# BLE-LORA-Relay-22dbm-v1-1.net
KiCad netlist of a schematic drawn in EAGLE
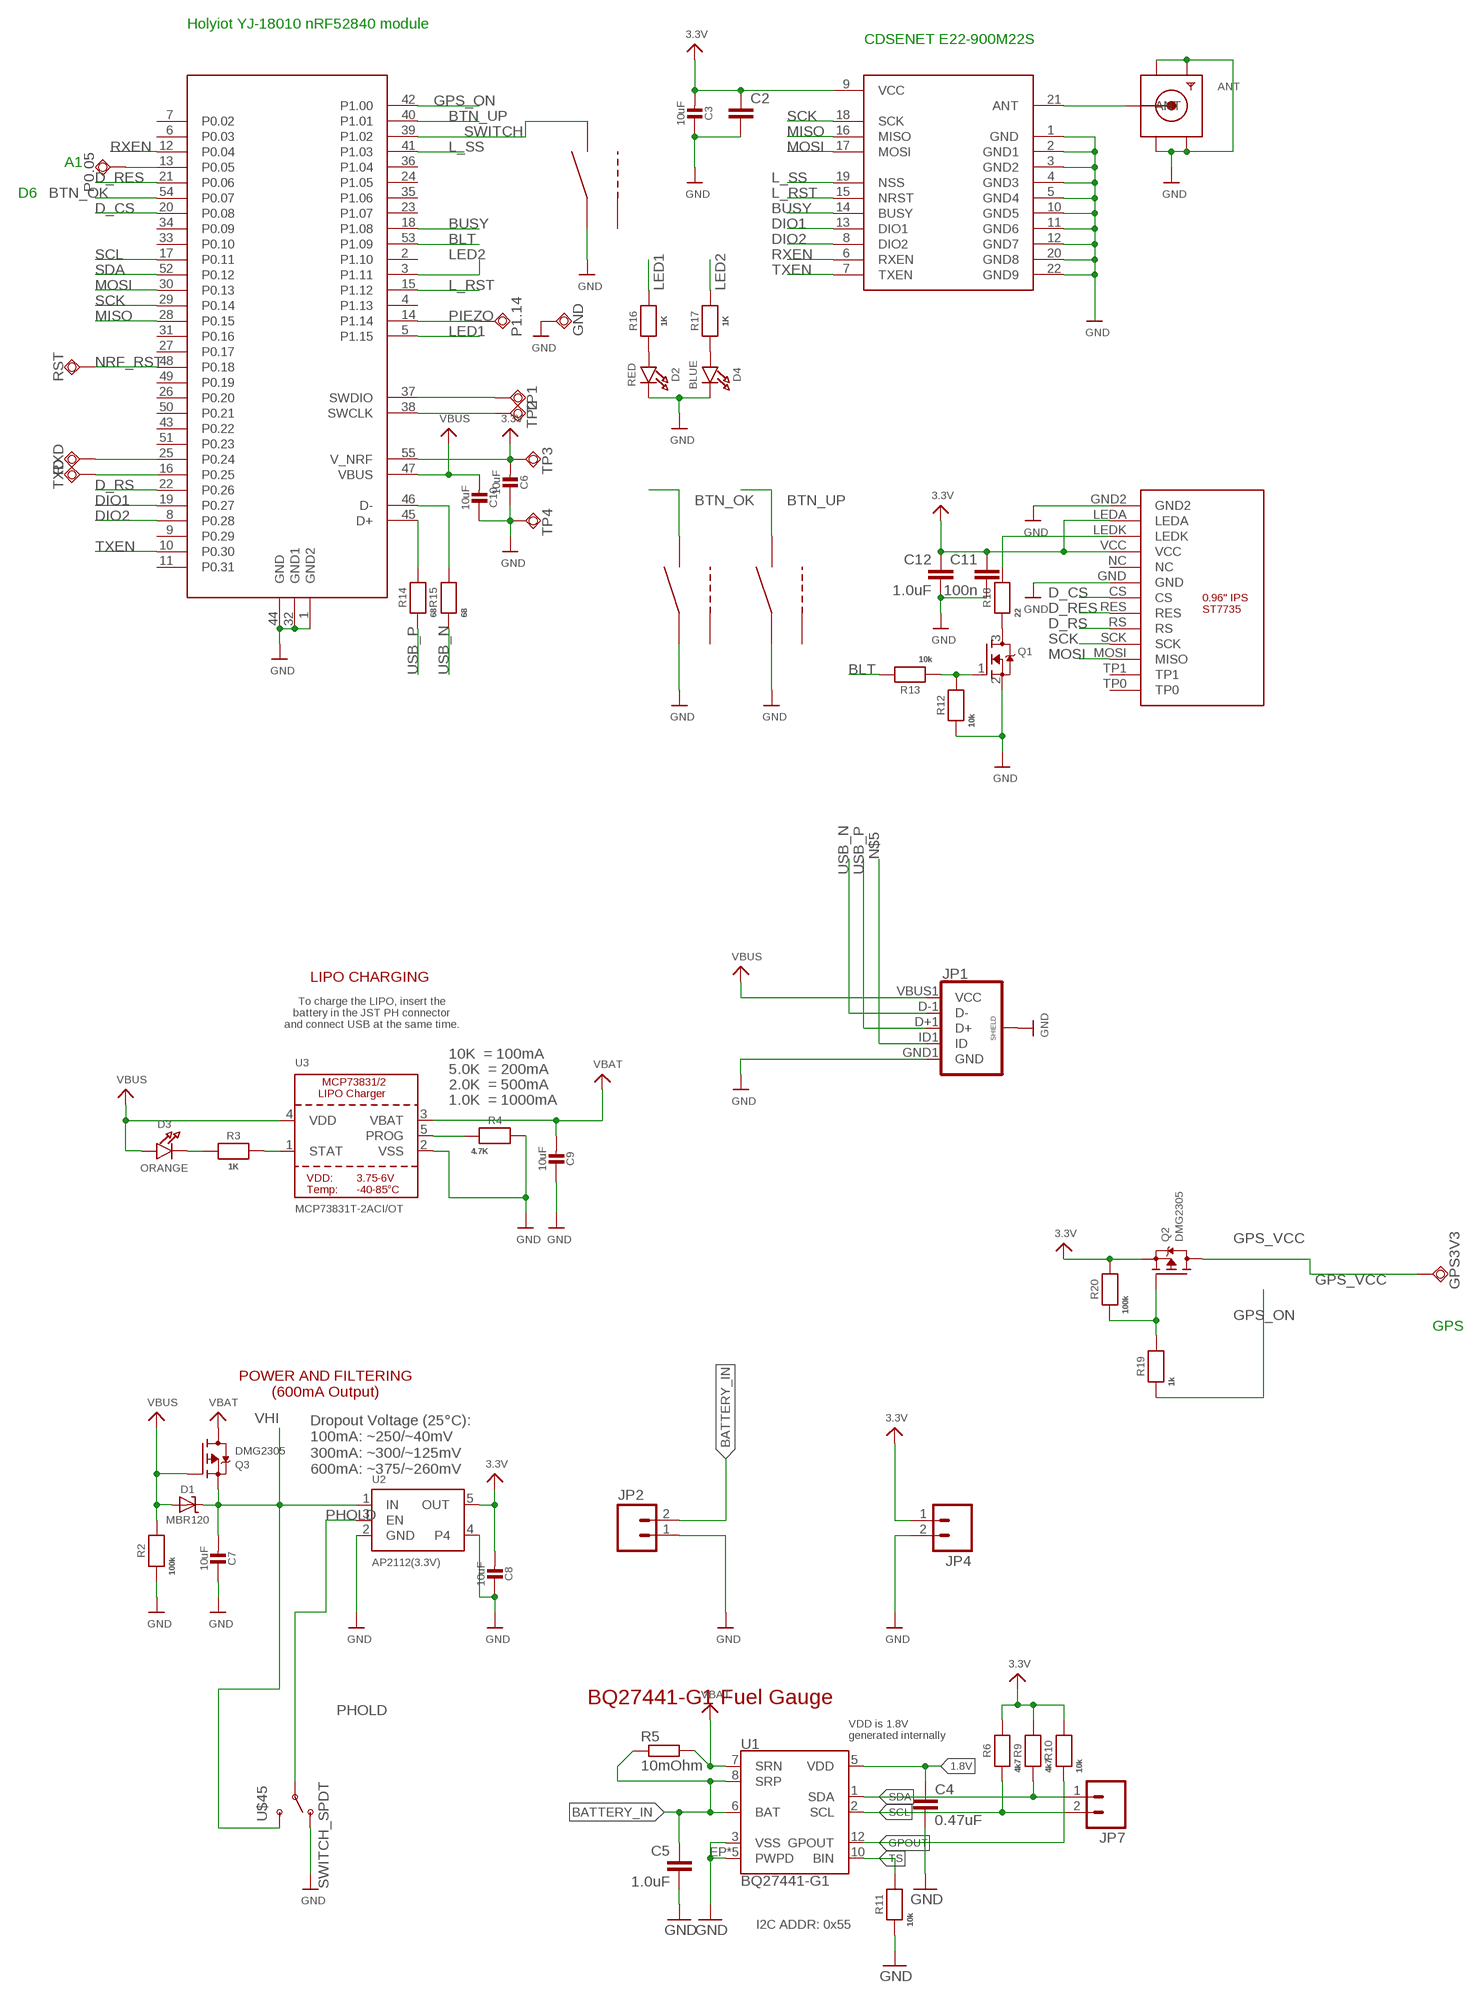
[diagram p0: schematic, sheet 1]

(export (version "E")
  (design (tool "Eeschema 10.0.6"))
  (components
    (comp (ref "ANT")
      (value "SMACONNECTOR_EDGE")
      (footprint "eagle-import:SMA_EDGELAUNCH")
      (libsource (lib "eagle-import") (part "SMACONNECTOR_EDGE"))
    )
    (comp (ref "C2")
      (value "C-EUC1206")
      (footprint "eagle-import:C1206")
      (libsource (lib "eagle-import") (part "C-EUC1206"))
    )
    (comp (ref "C3")
      (value "10uF")
      (footprint "eagle-import:0805-NO")
      (libsource (lib "eagle-import") (part "CAP_CERAMIC0805-NOOUTLINE"))
    )
    (comp (ref "C4")
      (value "0.47uF")
      (footprint "eagle-import:0603-CAP")
      (libsource (lib "eagle-import") (part "CAP0603-CAP"))
    )
    (comp (ref "C5")
      (value "1.0uF")
      (footprint "eagle-import:0603-CAP")
      (libsource (lib "eagle-import") (part "1.0UF-16V-10%(0603)"))
    )
    (comp (ref "C6")
      (value "10uF")
      (footprint "eagle-import:0805-NO")
      (libsource (lib "eagle-import") (part "CAP_CERAMIC0805-NOOUTLINE"))
    )
    (comp (ref "C7")
      (value "10uF")
      (footprint "eagle-import:0805-NO")
      (libsource (lib "eagle-import") (part "CAP_CERAMIC0805-NOOUTLINE"))
    )
    (comp (ref "C8")
      (value "10uF")
      (footprint "eagle-import:0805-NO")
      (libsource (lib "eagle-import") (part "CAP_CERAMIC0805-NOOUTLINE"))
    )
    (comp (ref "C9")
      (value "10uF")
      (footprint "eagle-import:0805-NO")
      (libsource (lib "eagle-import") (part "CAP_CERAMIC0805-NOOUTLINE"))
    )
    (comp (ref "C10")
      (value "10uF")
      (footprint "eagle-import:0805-NO")
      (libsource (lib "eagle-import") (part "CAP_CERAMIC0805-NOOUTLINE"))
    )
    (comp (ref "C11")
      (value "100n")
      (footprint "eagle-import:0603-CAP")
      (libsource (lib "eagle-import") (part "1.0UF-16V-10%(0603)"))
    )
    (comp (ref "C12")
      (value "1.0uF")
      (footprint "eagle-import:0603-CAP")
      (libsource (lib "eagle-import") (part "1.0UF-16V-10%(0603)"))
    )
    (comp (ref "D1")
      (value "MBR120")
      (footprint "eagle-import:SOD-123")
      (libsource (lib "eagle-import") (part "DIODE-SCHOTTKYSOD-123"))
    )
    (comp (ref "D2")
      (value "RED")
      (footprint "eagle-import:CHIPLED_0805_NOOUTLINE")
      (libsource (lib "eagle-import") (part "LED0805_NOOUTLINE"))
    )
    (comp (ref "D3")
      (value "ORANGE")
      (footprint "eagle-import:CHIPLED_0805_NOOUTLINE")
      (libsource (lib "eagle-import") (part "LED0805_NOOUTLINE"))
    )
    (comp (ref "D4")
      (value "BLUE")
      (footprint "eagle-import:CHIPLED_0805_NOOUTLINE")
      (libsource (lib "eagle-import") (part "LED0805_NOOUTLINE"))
    )
    (comp (ref "DWN")
      (value "LS12T2")
      (footprint "eagle-import:LS12T2")
      (libsource (lib "eagle-import") (part "LS12T2"))
    )
    (comp (ref "DWN1")
      (value "LS12T2")
      (footprint "eagle-import:LS12T2")
      (libsource (lib "eagle-import") (part "LS12T2"))
    )
    (comp (ref "DWN2")
      (value "LS12T2")
      (footprint "eagle-import:LS12T2")
      (libsource (lib "eagle-import") (part "LS12T2"))
    )
    (comp (ref "GND")
      (value "TPSQTP13R")
      (footprint "eagle-import:TP13R")
      (libsource (lib "eagle-import") (part "TPSQTP13R"))
    )
    (comp (ref "GPS3V3")
      (value "TPSQTP13R")
      (footprint "eagle-import:TP13R")
      (libsource (lib "eagle-import") (part "TPSQTP13R"))
    )
    (comp (ref "JP1")
      (value "USB_MICROB_PLUGCONN-11752")
      (footprint "eagle-import:USB-B-MICRO-SMD_V03")
      (libsource (lib "eagle-import") (part "USB_MICROB_PLUGCONN-11752"))
    )
    (comp (ref "JP2")
      (value "M02PTH")
      (footprint "eagle-import:1X02")
      (libsource (lib "eagle-import") (part "M02PTH"))
    )
    (comp (ref "JP4")
      (value "M02PTH")
      (footprint "eagle-import:1X02")
      (libsource (lib "eagle-import") (part "M02PTH"))
    )
    (comp (ref "JP7")
      (value "M02PTH")
      (footprint "eagle-import:1X02")
      (libsource (lib "eagle-import") (part "M02PTH"))
    )
    (comp (ref "P0.05")
      (value "TPSQTP13R")
      (footprint "eagle-import:TP13R")
      (libsource (lib "eagle-import") (part "TPSQTP13R"))
    )
    (comp (ref "P1.14")
      (value "TPSQTP13R")
      (footprint "eagle-import:TP13R")
      (libsource (lib "eagle-import") (part "TPSQTP13R"))
    )
    (comp (ref "Q1")
      (value "MOSFET-NREFLOW")
      (footprint "eagle-import:SOT23")
      (libsource (lib "eagle-import") (part "MOSFET-NREFLOW"))
    )
    (comp (ref "Q2")
      (value "DMG2305")
      (footprint "eagle-import:SOT23-R")
      (libsource (lib "eagle-import") (part "MOSFET-P"))
    )
    (comp (ref "Q3")
      (value "DMG2305")
      (footprint "eagle-import:SOT23-R")
      (libsource (lib "eagle-import") (part "MOSFET-P"))
    )
    (comp (ref "R2")
      (value "100k")
      (footprint "eagle-import:0603-NO")
      (libsource (lib "eagle-import") (part "RESISTOR_0603_NOOUT"))
    )
    (comp (ref "R3")
      (value "1K")
      (footprint "eagle-import:0603-NO")
      (libsource (lib "eagle-import") (part "RESISTOR_0603_NOOUT"))
    )
    (comp (ref "R4")
      (value "4.7K")
      (footprint "eagle-import:0603-NO")
      (libsource (lib "eagle-import") (part "RESISTOR_0603_NOOUT"))
    )
    (comp (ref "R5")
      (value "10mOhm")
      (footprint "eagle-import:R0805")
      (libsource (lib "eagle-import") (part "R-EU_R0805"))
    )
    (comp (ref "R6")
      (value "4k7")
      (footprint "eagle-import:0603-NO")
      (libsource (lib "eagle-import") (part "RESISTOR_0603_NOOUT"))
    )
    (comp (ref "R9")
      (value "4k7")
      (footprint "eagle-import:0603-NO")
      (libsource (lib "eagle-import") (part "RESISTOR_0603_NOOUT"))
    )
    (comp (ref "R10")
      (value "10k")
      (footprint "eagle-import:0603-NO")
      (libsource (lib "eagle-import") (part "RESISTOR_0603_NOOUT"))
    )
    (comp (ref "R11")
      (value "10k")
      (footprint "eagle-import:0603-NO")
      (libsource (lib "eagle-import") (part "RESISTOR_0603_NOOUT"))
    )
    (comp (ref "R12")
      (value "10k")
      (footprint "eagle-import:0603-NO")
      (libsource (lib "eagle-import") (part "RESISTOR_0603_NOOUT"))
    )
    (comp (ref "R13")
      (value "10k")
      (footprint "eagle-import:0603-NO")
      (libsource (lib "eagle-import") (part "RESISTOR_0603_NOOUT"))
    )
    (comp (ref "R14")
      (value "68")
      (footprint "eagle-import:0603-NO")
      (libsource (lib "eagle-import") (part "RESISTOR_0603_NOOUT"))
    )
    (comp (ref "R15")
      (value "68")
      (footprint "eagle-import:0603-NO")
      (libsource (lib "eagle-import") (part "RESISTOR_0603_NOOUT"))
    )
    (comp (ref "R16")
      (value "1K")
      (footprint "eagle-import:0603-NO")
      (libsource (lib "eagle-import") (part "RESISTOR_0603_NOOUT"))
    )
    (comp (ref "R17")
      (value "1K")
      (footprint "eagle-import:0603-NO")
      (libsource (lib "eagle-import") (part "RESISTOR_0603_NOOUT"))
    )
    (comp (ref "R18")
      (value "22")
      (footprint "eagle-import:0603-NO")
      (libsource (lib "eagle-import") (part "RESISTOR_0603_NOOUT"))
    )
    (comp (ref "R19")
      (value "1k")
      (footprint "eagle-import:0603-NO")
      (libsource (lib "eagle-import") (part "RESISTOR_0603_NOOUT"))
    )
    (comp (ref "R20")
      (value "100k")
      (footprint "eagle-import:0603-NO")
      (libsource (lib "eagle-import") (part "RESISTOR_0603_NOOUT"))
    )
    (comp (ref "RST")
      (value "TPSQTP13R")
      (footprint "eagle-import:TP13R")
      (libsource (lib "eagle-import") (part "TPSQTP13R"))
    )
    (comp (ref "RXD")
      (value "TPSQTP13R")
      (footprint "eagle-import:TP13R")
      (libsource (lib "eagle-import") (part "TPSQTP13R"))
    )
    (comp (ref "TP1")
      (value "TPSQTP13R")
      (footprint "eagle-import:TP13R")
      (libsource (lib "eagle-import") (part "TPSQTP13R"))
    )
    (comp (ref "TP2")
      (value "TPSQTP13R")
      (footprint "eagle-import:TP13R")
      (libsource (lib "eagle-import") (part "TPSQTP13R"))
    )
    (comp (ref "TP3")
      (value "TPSQTP13R")
      (footprint "eagle-import:TP13R")
      (libsource (lib "eagle-import") (part "TPSQTP13R"))
    )
    (comp (ref "TP4")
      (value "TPSQTP13R")
      (footprint "eagle-import:TP13R")
      (libsource (lib "eagle-import") (part "TPSQTP13R"))
    )
    (comp (ref "TXD")
      (value "TPSQTP13R")
      (footprint "eagle-import:TP13R")
      (libsource (lib "eagle-import") (part "TPSQTP13R"))
    )
    (comp (ref "U$14")
      (value "NRF52840")
      (footprint "eagle-import:NRF52840MOD")
      (libsource (lib "eagle-import") (part "NRF52840"))
    )
    (comp (ref "U$15")
      (value "SX1292-EBYTE")
      (footprint "eagle-import:SX1262_EBYTE")
      (libsource (lib "eagle-import") (part "SX1292-EBYTE"))
    )
    (comp (ref "U$16")
      (value "0.96_IPS")
      (footprint "eagle-import:0.96_IPS")
      (libsource (lib "eagle-import") (part "0.96_IPS"))
    )
    (comp (ref "U$45")
      (value "SWITCH_SPDT")
      (footprint "eagle-import:KPS-1290")
      (libsource (lib "eagle-import") (part "SWITCH_SPDT"))
    )
    (comp (ref "U1")
      (value "BQ27441-G1")
      (footprint "eagle-import:PDSO-N12")
      (libsource (lib "eagle-import") (part "BQ27441-G1"))
    )
    (comp (ref "U2")
      (value "AP2112(3.3V)")
      (footprint "eagle-import:SOT23-5")
      (libsource (lib "eagle-import") (part "VREG_SOT23-5"))
    )
    (comp (ref "U3")
      (value "MCP73831T-2ACI/OT")
      (footprint "eagle-import:SOT23-5")
      (libsource (lib "eagle-import") (part "MCP73831/2"))
    )
  )
  (nets
    (net (code "1") (name "/BLT") (class "Default")
      (node (ref "R13") (pin "2") (pinfunction "2_2") (pintype "passive"))
      (node (ref "U$14") (pin "53") (pinfunction "P1.09_53") (pintype "bidirectional"))
    )
    (net (code "2") (name "/BTN_OK") (class "Default")
      (node (ref "DWN2") (pin "1") (pinfunction "1_1") (pintype "bidirectional"))
      (node (ref "U$14") (pin "54") (pinfunction "P0.07_54") (pintype "bidirectional"))
    )
    (net (code "3") (name "/BTN_UP") (class "Default")
      (node (ref "DWN") (pin "1") (pinfunction "1_1") (pintype "bidirectional"))
      (node (ref "U$14") (pin "40") (pinfunction "P1.01_40") (pintype "bidirectional"))
    )
    (net (code "4") (name "/BUSY") (class "Default")
      (node (ref "U$14") (pin "18") (pinfunction "P1.08_18") (pintype "bidirectional"))
      (node (ref "U$15") (pin "14") (pinfunction "BUSY_14") (pintype "bidirectional"))
    )
    (net (code "5") (name "/DIO1") (class "Default")
      (node (ref "U$14") (pin "19") (pinfunction "P0.27_19") (pintype "bidirectional"))
      (node (ref "U$15") (pin "13") (pinfunction "DIO1_13") (pintype "bidirectional"))
    )
    (net (code "6") (name "/DIO2") (class "Default")
      (node (ref "U$14") (pin "8") (pinfunction "P0.28_8") (pintype "bidirectional"))
      (node (ref "U$15") (pin "8") (pinfunction "DIO2_8") (pintype "bidirectional"))
    )
    (net (code "7") (name "/D_CS") (class "Default")
      (node (ref "U$14") (pin "20") (pinfunction "P0.08_20") (pintype "bidirectional"))
      (node (ref "U$16") (pin "CS") (pinfunction "CS_CS") (pintype "bidirectional"))
    )
    (net (code "8") (name "/D_RES") (class "Default")
      (node (ref "U$14") (pin "21") (pinfunction "P0.06_21") (pintype "bidirectional"))
      (node (ref "U$16") (pin "RES") (pinfunction "RES_RES") (pintype "bidirectional"))
    )
    (net (code "9") (name "/D_RS") (class "Default")
      (node (ref "U$14") (pin "22") (pinfunction "P0.26_22") (pintype "bidirectional"))
      (node (ref "U$16") (pin "RS") (pinfunction "RS_RS") (pintype "bidirectional"))
    )
    (net (code "10") (name "/GPS_ON") (class "Default")
      (node (ref "R19") (pin "1") (pinfunction "1_1") (pintype "passive"))
      (node (ref "U$14") (pin "42") (pinfunction "P1.00_42") (pintype "bidirectional"))
    )
    (net (code "11") (name "/GPS_VCC") (class "Default")
      (node (ref "GPS3V3") (pin "TP") (pinfunction "TP_TP") (pintype "input"))
      (node (ref "Q2") (pin "3") (pinfunction "D_3") (pintype "passive"))
    )
    (net (code "12") (name "/LED1") (class "Default")
      (node (ref "R16") (pin "2") (pinfunction "2_2") (pintype "passive"))
      (node (ref "U$14") (pin "5") (pinfunction "P1.15_5") (pintype "bidirectional"))
    )
    (net (code "13") (name "/LED2") (class "Default")
      (node (ref "R17") (pin "2") (pinfunction "2_2") (pintype "passive"))
      (node (ref "U$14") (pin "3") (pinfunction "P1.11_3") (pintype "bidirectional"))
    )
    (net (code "14") (name "/L_RST") (class "Default")
      (node (ref "U$14") (pin "15") (pinfunction "P1.12_15") (pintype "bidirectional"))
      (node (ref "U$15") (pin "15") (pinfunction "NRST_15") (pintype "bidirectional"))
    )
    (net (code "15") (name "/L_SS") (class "Default")
      (node (ref "U$14") (pin "41") (pinfunction "P1.03_41") (pintype "bidirectional"))
      (node (ref "U$15") (pin "19") (pinfunction "NSS_19") (pintype "bidirectional"))
    )
    (net (code "16") (name "/MISO") (class "Default")
      (node (ref "U$14") (pin "28") (pinfunction "P0.15_28") (pintype "bidirectional"))
      (node (ref "U$15") (pin "16") (pinfunction "MISO_16") (pintype "bidirectional"))
    )
    (net (code "17") (name "/MOSI") (class "Default")
      (node (ref "U$14") (pin "30") (pinfunction "P0.13_30") (pintype "bidirectional"))
      (node (ref "U$15") (pin "17") (pinfunction "MOSI_17") (pintype "bidirectional"))
      (node (ref "U$16") (pin "MOSI") (pinfunction "MISO_MOSI") (pintype "bidirectional"))
    )
    (net (code "18") (name "/N$5") (class "Default")
      (node (ref "JP1") (pin "ID1") (pinfunction "ID_ID1") (pintype "bidirectional"))
    )
    (net (code "19") (name "/NRF_RST") (class "Default")
      (node (ref "RST") (pin "TP") (pinfunction "TP_TP") (pintype "input"))
      (node (ref "U$14") (pin "48") (pinfunction "P0.18_48") (pintype "bidirectional"))
    )
    (net (code "20") (name "/PHOLD") (class "Default")
      (node (ref "U$45") (pin "P") (pinfunction "P_P") (pintype "passive"))
      (node (ref "U2") (pin "3") (pinfunction "EN_3") (pintype "input"))
    )
    (net (code "21") (name "/PIEZO") (class "Default")
      (node (ref "P1.14") (pin "TP") (pinfunction "TP_TP") (pintype "input"))
      (node (ref "U$14") (pin "14") (pinfunction "P1.14_14") (pintype "bidirectional"))
    )
    (net (code "22") (name "/RXEN") (class "Default")
      (node (ref "U$14") (pin "12") (pinfunction "P0.04_12") (pintype "bidirectional"))
      (node (ref "U$15") (pin "6") (pinfunction "RXEN_6") (pintype "bidirectional"))
    )
    (net (code "23") (name "/SCK") (class "Default")
      (node (ref "U$14") (pin "29") (pinfunction "P0.14_29") (pintype "bidirectional"))
      (node (ref "U$15") (pin "18") (pinfunction "SCK_18") (pintype "bidirectional"))
      (node (ref "U$16") (pin "SCK") (pinfunction "SCK_SCK") (pintype "bidirectional"))
    )
    (net (code "24") (name "/SWITCH") (class "Default")
      (node (ref "DWN1") (pin "1") (pinfunction "1_1") (pintype "bidirectional"))
      (node (ref "U$14") (pin "39") (pinfunction "P1.02_39") (pintype "bidirectional"))
    )
    (net (code "25") (name "/TXEN") (class "Default")
      (node (ref "U$14") (pin "10") (pinfunction "P0.30_10") (pintype "bidirectional"))
      (node (ref "U$15") (pin "7") (pinfunction "TXEN_7") (pintype "bidirectional"))
    )
    (net (code "26") (name "/USB_N") (class "Default")
      (node (ref "JP1") (pin "D-1") (pinfunction "D-_D-1") (pintype "bidirectional"))
      (node (ref "R15") (pin "1") (pinfunction "1_1") (pintype "passive"))
    )
    (net (code "27") (name "/USB_P") (class "Default")
      (node (ref "JP1") (pin "D+1") (pinfunction "D+_D+1") (pintype "bidirectional"))
      (node (ref "R14") (pin "1") (pinfunction "1_1") (pintype "passive"))
    )
    (net (code "28") (name "/VHI") (class "Default")
      (node (ref "C7") (pin "2") (pinfunction "2_2") (pintype "passive"))
      (node (ref "D1") (pin "C") (pinfunction "C_C") (pintype "passive"))
      (node (ref "Q3") (pin "2") (pinfunction "S_2") (pintype "passive"))
      (node (ref "U$45") (pin "S") (pinfunction "S_S") (pintype "passive"))
      (node (ref "U2") (pin "1") (pinfunction "IN_1") (pintype "power_in"))
    )
    (net (code "29") (name "1.8V") (class "Default")
      (node (ref "C4") (pin "1") (pinfunction "1_1") (pintype "passive"))
      (node (ref "U1") (pin "5") (pinfunction "VDD_5") (pintype "bidirectional"))
    )
    (net (code "30") (name "3.3V") (class "Default")
      (node (ref "C11") (pin "1") (pinfunction "1_1") (pintype "passive"))
      (node (ref "C12") (pin "1") (pinfunction "1_1") (pintype "passive"))
      (node (ref "C2") (pin "1") (pinfunction "1_1") (pintype "passive"))
      (node (ref "C3") (pin "2") (pinfunction "2_2") (pintype "passive"))
      (node (ref "C6") (pin "2") (pinfunction "2_2") (pintype "passive"))
      (node (ref "C8") (pin "2") (pinfunction "2_2") (pintype "passive"))
      (node (ref "JP4") (pin "1") (pinfunction "1_1") (pintype "passive"))
      (node (ref "Q2") (pin "2") (pinfunction "S_2") (pintype "passive"))
      (node (ref "R10") (pin "2") (pinfunction "2_2") (pintype "passive"))
      (node (ref "R20") (pin "2") (pinfunction "2_2") (pintype "passive"))
      (node (ref "R6") (pin "2") (pinfunction "2_2") (pintype "passive"))
      (node (ref "R9") (pin "2") (pinfunction "2_2") (pintype "passive"))
      (node (ref "TP3") (pin "TP") (pinfunction "TP_TP") (pintype "input"))
      (node (ref "U$14") (pin "55") (pinfunction "V_NRF_55") (pintype "bidirectional"))
      (node (ref "U$15") (pin "9") (pinfunction "VCC_9") (pintype "bidirectional"))
      (node (ref "U$16") (pin "LEDA") (pinfunction "LEDA_LEDA") (pintype "bidirectional"))
      (node (ref "U$16") (pin "VCC") (pinfunction "VCC_VCC") (pintype "bidirectional"))
      (node (ref "U2") (pin "5") (pinfunction "OUT_5") (pintype "power_in"))
    )
    (net (code "31") (name "BATTERY_IN") (class "Default")
      (node (ref "C5") (pin "1") (pinfunction "1_1") (pintype "passive"))
      (node (ref "JP2") (pin "2") (pinfunction "2_2") (pintype "passive"))
      (node (ref "R5") (pin "1") (pinfunction "1_1") (pintype "passive"))
      (node (ref "U1") (pin "6") (pinfunction "BAT_6") (pintype "bidirectional"))
      (node (ref "U1") (pin "8") (pinfunction "SRP_8") (pintype "bidirectional"))
    )
    (net (code "32") (name "GND") (class "Default")
      (node (ref "ANT") (pin "GND@1") (pinfunction "GND4_GND@1") (pintype "power_in"))
      (node (ref "ANT") (pin "GND@2") (pinfunction "GND3_GND@2") (pintype "power_in"))
      (node (ref "ANT") (pin "GND@3") (pinfunction "GND2_GND@3") (pintype "power_in"))
      (node (ref "ANT") (pin "GND@4") (pinfunction "GND1_GND@4") (pintype "power_in"))
      (node (ref "C10") (pin "1") (pinfunction "1_1") (pintype "passive"))
      (node (ref "C11") (pin "2") (pinfunction "2_2") (pintype "passive"))
      (node (ref "C12") (pin "2") (pinfunction "2_2") (pintype "passive"))
      (node (ref "C2") (pin "2") (pinfunction "2_2") (pintype "passive"))
      (node (ref "C3") (pin "1") (pinfunction "1_1") (pintype "passive"))
      (node (ref "C4") (pin "2") (pinfunction "2_2") (pintype "passive"))
      (node (ref "C5") (pin "2") (pinfunction "2_2") (pintype "passive"))
      (node (ref "C6") (pin "1") (pinfunction "1_1") (pintype "passive"))
      (node (ref "C7") (pin "1") (pinfunction "1_1") (pintype "passive"))
      (node (ref "C8") (pin "1") (pinfunction "1_1") (pintype "passive"))
      (node (ref "C9") (pin "1") (pinfunction "1_1") (pintype "passive"))
      (node (ref "D2") (pin "C") (pinfunction "C_C") (pintype "passive"))
      (node (ref "D4") (pin "C") (pinfunction "C_C") (pintype "passive"))
      (node (ref "DWN") (pin "2") (pinfunction "2_2") (pintype "bidirectional"))
      (node (ref "DWN1") (pin "2") (pinfunction "2_2") (pintype "bidirectional"))
      (node (ref "DWN2") (pin "2") (pinfunction "2_2") (pintype "bidirectional"))
      (node (ref "GND") (pin "TP") (pinfunction "TP_TP") (pintype "input"))
      (node (ref "JP1") (pin "GND1") (pinfunction "GND_GND1") (pintype "bidirectional"))
      (node (ref "JP1") (pin "SHIELD1") (pinfunction "SHIELD_SHIELD1") (pintype "bidirectional"))
      (node (ref "JP1") (pin "SHIELD2") (pinfunction "SHIELD_SHIELD2") (pintype "bidirectional"))
      (node (ref "JP1") (pin "SHIELD3") (pinfunction "SHIELD_SHIELD3") (pintype "bidirectional"))
      (node (ref "JP2") (pin "1") (pinfunction "1_1") (pintype "passive"))
      (node (ref "JP4") (pin "2") (pinfunction "2_2") (pintype "passive"))
      (node (ref "Q1") (pin "2") (pinfunction "S_2") (pintype "bidirectional"))
      (node (ref "R11") (pin "1") (pinfunction "1_1") (pintype "passive"))
      (node (ref "R12") (pin "1") (pinfunction "1_1") (pintype "passive"))
      (node (ref "R2") (pin "1") (pinfunction "1_1") (pintype "passive"))
      (node (ref "R4") (pin "2") (pinfunction "2_2") (pintype "passive"))
      (node (ref "TP4") (pin "TP") (pinfunction "TP_TP") (pintype "input"))
      (node (ref "U$14") (pin "1") (pinfunction "GND2_1") (pintype "bidirectional"))
      (node (ref "U$14") (pin "32") (pinfunction "GND1_32") (pintype "bidirectional"))
      (node (ref "U$14") (pin "44") (pinfunction "GND_44") (pintype "bidirectional"))
      (node (ref "U$15") (pin "1") (pinfunction "GND_1") (pintype "bidirectional"))
      (node (ref "U$15") (pin "10") (pinfunction "GND5_10") (pintype "bidirectional"))
      (node (ref "U$15") (pin "11") (pinfunction "GND6_11") (pintype "bidirectional"))
      (node (ref "U$15") (pin "12") (pinfunction "GND7_12") (pintype "bidirectional"))
      (node (ref "U$15") (pin "2") (pinfunction "GND1_2") (pintype "bidirectional"))
      (node (ref "U$15") (pin "20") (pinfunction "GND8_20") (pintype "bidirectional"))
      (node (ref "U$15") (pin "22") (pinfunction "GND9_22") (pintype "bidirectional"))
      (node (ref "U$15") (pin "3") (pinfunction "GND2_3") (pintype "bidirectional"))
      (node (ref "U$15") (pin "4") (pinfunction "GND3_4") (pintype "bidirectional"))
      (node (ref "U$15") (pin "5") (pinfunction "GND4_5") (pintype "bidirectional"))
      (node (ref "U$16") (pin "GND") (pinfunction "GND_GND") (pintype "bidirectional"))
      (node (ref "U$16") (pin "GND2") (pinfunction "GND2_GND2") (pintype "bidirectional"))
      (node (ref "U$45") (pin "O") (pinfunction "O_O") (pintype "passive"))
      (node (ref "U1") (pin "3") (pinfunction "VSS_3") (pintype "bidirectional"))
      (node (ref "U1") (pin "EP") (pinfunction "PWPD_EP") (pintype "bidirectional"))
      (node (ref "U1") (pin "EP1") (pinfunction "PWPD_EP1") (pintype "bidirectional"))
      (node (ref "U1") (pin "EP2") (pinfunction "PWPD_EP2") (pintype "bidirectional"))
      (node (ref "U1") (pin "EP3") (pinfunction "PWPD_EP3") (pintype "bidirectional"))
      (node (ref "U1") (pin "EP4") (pinfunction "PWPD_EP4") (pintype "bidirectional"))
      (node (ref "U2") (pin "2") (pinfunction "GND_2") (pintype "power_in"))
      (node (ref "U2") (pin "4") (pinfunction "P4_4") (pintype "bidirectional"))
      (node (ref "U3") (pin "2") (pinfunction "VSS_2") (pintype "power_in"))
    )
    (net (code "33") (name "GPOUT") (class "Default")
      (node (ref "R10") (pin "1") (pinfunction "1_1") (pintype "passive"))
      (node (ref "U1") (pin "12") (pinfunction "GPOUT_12") (pintype "bidirectional"))
    )
    (net (code "34") (name "Net-(ANT-ANT)") (class "Default")
      (node (ref "ANT") (pin "P") (pinfunction "ANT_P") (pintype "bidirectional"))
      (node (ref "U$15") (pin "21") (pinfunction "ANT_21") (pintype "bidirectional"))
    )
    (net (code "35") (name "Net-(D2-PadA)") (class "Default")
      (node (ref "D2") (pin "A") (pinfunction "A_A") (pintype "passive"))
      (node (ref "R16") (pin "1") (pinfunction "1_1") (pintype "passive"))
    )
    (net (code "36") (name "Net-(D3-PadC)") (class "Default")
      (node (ref "D3") (pin "C") (pinfunction "C_C") (pintype "passive"))
      (node (ref "R3") (pin "1") (pinfunction "1_1") (pintype "passive"))
    )
    (net (code "37") (name "Net-(D4-PadA)") (class "Default")
      (node (ref "D4") (pin "A") (pinfunction "A_A") (pintype "passive"))
      (node (ref "R17") (pin "1") (pinfunction "1_1") (pintype "passive"))
    )
    (net (code "38") (name "Net-(Q1-D)") (class "Default")
      (node (ref "Q1") (pin "3") (pinfunction "D_3") (pintype "bidirectional"))
      (node (ref "R18") (pin "1") (pinfunction "1_1") (pintype "passive"))
    )
    (net (code "39") (name "Net-(Q1-G)") (class "Default")
      (node (ref "Q1") (pin "1") (pinfunction "G_1") (pintype "bidirectional"))
      (node (ref "R12") (pin "2") (pinfunction "2_2") (pintype "passive"))
      (node (ref "R13") (pin "1") (pinfunction "1_1") (pintype "passive"))
    )
    (net (code "40") (name "Net-(Q2-G)") (class "Default")
      (node (ref "Q2") (pin "1") (pinfunction "G_1") (pintype "passive"))
      (node (ref "R19") (pin "2") (pinfunction "2_2") (pintype "passive"))
      (node (ref "R20") (pin "1") (pinfunction "1_1") (pintype "passive"))
    )
    (net (code "41") (name "Net-(R18-Pad2)") (class "Default")
      (node (ref "R18") (pin "2") (pinfunction "2_2") (pintype "passive"))
      (node (ref "U$16") (pin "LEDK") (pinfunction "LEDK_LEDK") (pintype "bidirectional"))
    )
    (net (code "42") (name "Net-(U$14-D+)") (class "Default")
      (node (ref "R14") (pin "2") (pinfunction "2_2") (pintype "passive"))
      (node (ref "U$14") (pin "45") (pinfunction "D+_45") (pintype "bidirectional"))
    )
    (net (code "43") (name "Net-(U$14-D-)") (class "Default")
      (node (ref "R15") (pin "2") (pinfunction "2_2") (pintype "passive"))
      (node (ref "U$14") (pin "46") (pinfunction "D-_46") (pintype "bidirectional"))
    )
    (net (code "44") (name "Net-(U$14-P0.05)") (class "Default")
      (node (ref "P0.05") (pin "TP") (pinfunction "TP_TP") (pintype "input"))
      (node (ref "U$14") (pin "13") (pinfunction "P0.05_13") (pintype "bidirectional"))
    )
    (net (code "45") (name "Net-(U$14-P0.24)") (class "Default")
      (node (ref "RXD") (pin "TP") (pinfunction "TP_TP") (pintype "input"))
      (node (ref "U$14") (pin "25") (pinfunction "P0.24_25") (pintype "bidirectional"))
    )
    (net (code "46") (name "Net-(U$14-P0.25)") (class "Default")
      (node (ref "TXD") (pin "TP") (pinfunction "TP_TP") (pintype "input"))
      (node (ref "U$14") (pin "16") (pinfunction "P0.25_16") (pintype "bidirectional"))
    )
    (net (code "47") (name "Net-(U$14-SWCLK)") (class "Default")
      (node (ref "TP2") (pin "TP") (pinfunction "TP_TP") (pintype "input"))
      (node (ref "U$14") (pin "38") (pinfunction "SWCLK_38") (pintype "bidirectional"))
    )
    (net (code "48") (name "Net-(U$14-SWDIO)") (class "Default")
      (node (ref "TP1") (pin "TP") (pinfunction "TP_TP") (pintype "input"))
      (node (ref "U$14") (pin "37") (pinfunction "SWDIO_37") (pintype "bidirectional"))
    )
    (net (code "49") (name "Net-(U3-PROG)") (class "Default")
      (node (ref "R4") (pin "1") (pinfunction "1_1") (pintype "passive"))
      (node (ref "U3") (pin "5") (pinfunction "PROG_5") (pintype "input"))
    )
    (net (code "50") (name "Net-(U3-STAT)") (class "Default")
      (node (ref "R3") (pin "2") (pinfunction "2_2") (pintype "passive"))
      (node (ref "U3") (pin "1") (pinfunction "STAT_1") (pintype "output"))
    )
    (net (code "51") (name "SCL") (class "Default")
      (node (ref "JP7") (pin "2") (pinfunction "2_2") (pintype "passive"))
      (node (ref "R6") (pin "1") (pinfunction "1_1") (pintype "passive"))
      (node (ref "U$14") (pin "17") (pinfunction "P0.11_17") (pintype "bidirectional"))
      (node (ref "U1") (pin "2") (pinfunction "SCL_2") (pintype "bidirectional"))
    )
    (net (code "52") (name "SDA") (class "Default")
      (node (ref "JP7") (pin "1") (pinfunction "1_1") (pintype "passive"))
      (node (ref "R9") (pin "1") (pinfunction "1_1") (pintype "passive"))
      (node (ref "U$14") (pin "52") (pinfunction "P0.12_52") (pintype "bidirectional"))
      (node (ref "U1") (pin "1") (pinfunction "SDA_1") (pintype "bidirectional"))
    )
    (net (code "53") (name "TS") (class "Default")
      (node (ref "R11") (pin "2") (pinfunction "2_2") (pintype "passive"))
      (node (ref "U1") (pin "10") (pinfunction "BIN_10") (pintype "bidirectional"))
    )
    (net (code "54") (name "VBAT") (class "Default")
      (node (ref "C9") (pin "2") (pinfunction "2_2") (pintype "passive"))
      (node (ref "Q3") (pin "3") (pinfunction "D_3") (pintype "passive"))
      (node (ref "R5") (pin "2") (pinfunction "2_2") (pintype "passive"))
      (node (ref "U1") (pin "7") (pinfunction "SRN_7") (pintype "bidirectional"))
      (node (ref "U3") (pin "3") (pinfunction "VBAT_3") (pintype "power_in"))
    )
    (net (code "55") (name "VBUS") (class "Default")
      (node (ref "C10") (pin "2") (pinfunction "2_2") (pintype "passive"))
      (node (ref "D1") (pin "A") (pinfunction "A_A") (pintype "passive"))
      (node (ref "D3") (pin "A") (pinfunction "A_A") (pintype "passive"))
      (node (ref "JP1") (pin "VBUS1") (pinfunction "VCC_VBUS1") (pintype "bidirectional"))
      (node (ref "Q3") (pin "1") (pinfunction "G_1") (pintype "passive"))
      (node (ref "R2") (pin "2") (pinfunction "2_2") (pintype "passive"))
      (node (ref "U$14") (pin "47") (pinfunction "VBUS_47") (pintype "bidirectional"))
      (node (ref "U3") (pin "4") (pinfunction "VDD_4") (pintype "power_in"))
    )
    (net (code "56") (name "unconnected-(DWN-FRM-PadFRAME)") (class "Default")
      (node (ref "DWN") (pin "FRAME") (pinfunction "FRM_FRAME") (pintype "bidirectional"))
    )
    (net (code "57") (name "unconnected-(DWN1-FRM-PadFRAME)") (class "Default")
      (node (ref "DWN1") (pin "FRAME") (pinfunction "FRM_FRAME") (pintype "bidirectional"))
    )
    (net (code "58") (name "unconnected-(DWN2-FRM-PadFRAME)") (class "Default")
      (node (ref "DWN2") (pin "FRAME") (pinfunction "FRM_FRAME") (pintype "bidirectional"))
    )
    (net (code "59") (name "unconnected-(U$14-P0.02-Pad7)") (class "Default")
      (node (ref "U$14") (pin "7") (pinfunction "P0.02_7") (pintype "bidirectional"))
    )
    (net (code "60") (name "unconnected-(U$14-P0.03-Pad6)") (class "Default")
      (node (ref "U$14") (pin "6") (pinfunction "P0.03_6") (pintype "bidirectional"))
    )
    (net (code "61") (name "unconnected-(U$14-P0.09-Pad34)") (class "Default")
      (node (ref "U$14") (pin "34") (pinfunction "P0.09_34") (pintype "bidirectional"))
    )
    (net (code "62") (name "unconnected-(U$14-P0.10-Pad33)") (class "Default")
      (node (ref "U$14") (pin "33") (pinfunction "P0.10_33") (pintype "bidirectional"))
    )
    (net (code "63") (name "unconnected-(U$14-P0.16-Pad31)") (class "Default")
      (node (ref "U$14") (pin "31") (pinfunction "P0.16_31") (pintype "bidirectional"))
    )
    (net (code "64") (name "unconnected-(U$14-P0.17-Pad27)") (class "Default")
      (node (ref "U$14") (pin "27") (pinfunction "P0.17_27") (pintype "bidirectional"))
    )
    (net (code "65") (name "unconnected-(U$14-P0.19-Pad49)") (class "Default")
      (node (ref "U$14") (pin "49") (pinfunction "P0.19_49") (pintype "bidirectional"))
    )
    (net (code "66") (name "unconnected-(U$14-P0.20-Pad26)") (class "Default")
      (node (ref "U$14") (pin "26") (pinfunction "P0.20_26") (pintype "bidirectional"))
    )
    (net (code "67") (name "unconnected-(U$14-P0.21-Pad50)") (class "Default")
      (node (ref "U$14") (pin "50") (pinfunction "P0.21_50") (pintype "bidirectional"))
    )
    (net (code "68") (name "unconnected-(U$14-P0.22-Pad43)") (class "Default")
      (node (ref "U$14") (pin "43") (pinfunction "P0.22_43") (pintype "bidirectional"))
    )
    (net (code "69") (name "unconnected-(U$14-P0.23-Pad51)") (class "Default")
      (node (ref "U$14") (pin "51") (pinfunction "P0.23_51") (pintype "bidirectional"))
    )
    (net (code "70") (name "unconnected-(U$14-P0.29-Pad9)") (class "Default")
      (node (ref "U$14") (pin "9") (pinfunction "P0.29_9") (pintype "bidirectional"))
    )
    (net (code "71") (name "unconnected-(U$14-P0.31-Pad11)") (class "Default")
      (node (ref "U$14") (pin "11") (pinfunction "P0.31_11") (pintype "bidirectional"))
    )
    (net (code "72") (name "unconnected-(U$14-P1.04-Pad36)") (class "Default")
      (node (ref "U$14") (pin "36") (pinfunction "P1.04_36") (pintype "bidirectional"))
    )
    (net (code "73") (name "unconnected-(U$14-P1.05-Pad24)") (class "Default")
      (node (ref "U$14") (pin "24") (pinfunction "P1.05_24") (pintype "bidirectional"))
    )
    (net (code "74") (name "unconnected-(U$14-P1.06-Pad35)") (class "Default")
      (node (ref "U$14") (pin "35") (pinfunction "P1.06_35") (pintype "bidirectional"))
    )
    (net (code "75") (name "unconnected-(U$14-P1.07-Pad23)") (class "Default")
      (node (ref "U$14") (pin "23") (pinfunction "P1.07_23") (pintype "bidirectional"))
    )
    (net (code "76") (name "unconnected-(U$14-P1.10-Pad2)") (class "Default")
      (node (ref "U$14") (pin "2") (pinfunction "P1.10_2") (pintype "bidirectional"))
    )
    (net (code "77") (name "unconnected-(U$14-P1.13-Pad4)") (class "Default")
      (node (ref "U$14") (pin "4") (pinfunction "P1.13_4") (pintype "bidirectional"))
    )
    (net (code "78") (name "unconnected-(U$16-PadNC)") (class "Default")
      (node (ref "U$16") (pin "NC") (pinfunction "NC_NC") (pintype "bidirectional"))
    )
    (net (code "79") (name "unconnected-(U$16-PadTP0)") (class "Default")
      (node (ref "U$16") (pin "TP0") (pinfunction "TP0_TP0") (pintype "bidirectional"))
    )
    (net (code "80") (name "unconnected-(U$16-PadTP1)") (class "Default")
      (node (ref "U$16") (pin "TP1") (pinfunction "TP1_TP1") (pintype "bidirectional"))
    )
  )
)
